# MK12_RelayShield.net
KiCad netlist of a schematic drawn in EAGLE
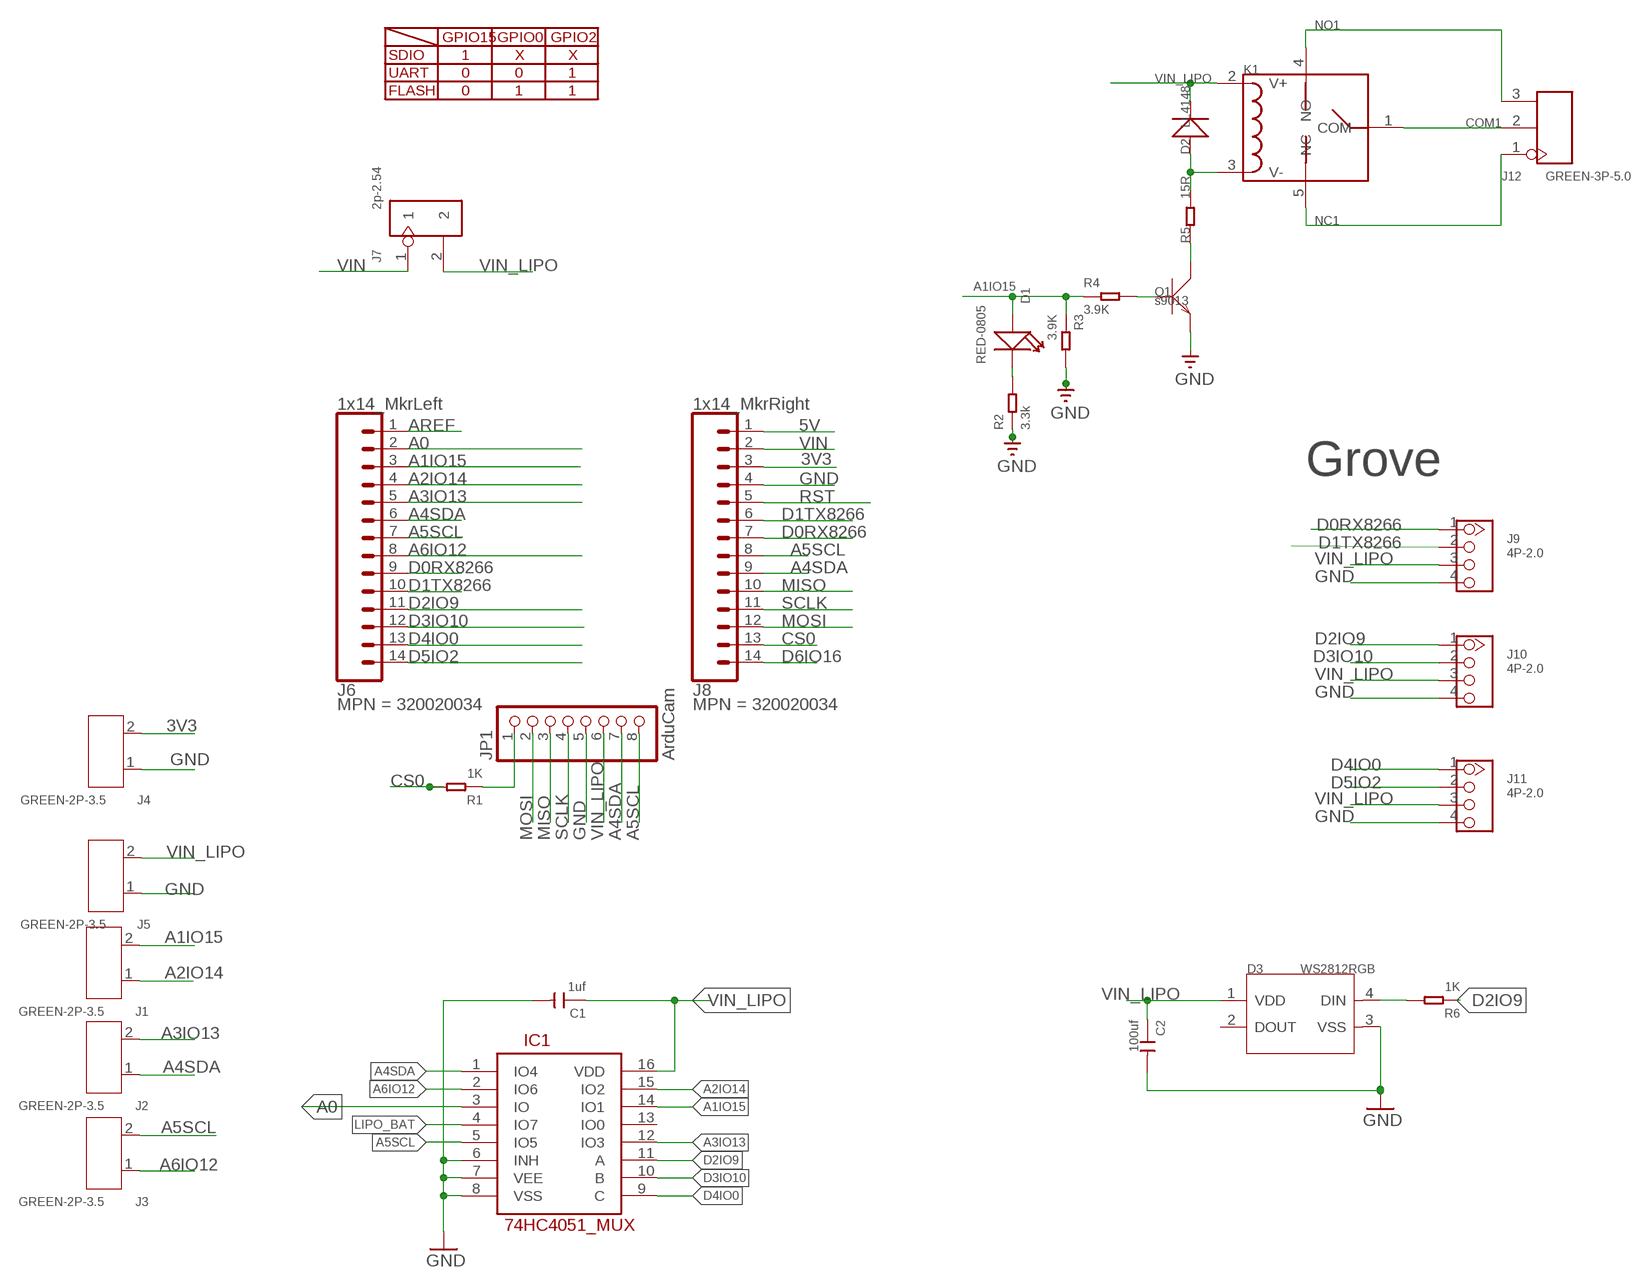
[diagram p0: schematic, sheet 1]

(export (version "E")
  (design (tool "Eeschema 10.0.6"))
  (components
    (comp (ref "C1")
      (value "1uf")
      (footprint "eagle-import:C0603")
      (fields (field (name "MPN") "CC0603KRX7R8BB105"))
      (libsource (lib "eagle-import") (part "CERAMIC-1UF-25V-10%-X7R(0603)"))
    )
    (comp (ref "C2")
      (value "100uf")
      (footprint "eagle-import:C1206")
      (fields (field (name "MPN") "GRM31CR60J107ME39L"))
      (libsource (lib "eagle-import") (part "CERAMIC-100UF-6.3V-20%-X5R(1206)"))
    )
    (comp (ref "D1")
      (value "RED-0805")
      (footprint "eagle-import:LED-0805")
      (fields (field (name "MPN") "17-215SURC/S530-A2/TR8"))
      (libsource (lib "eagle-import") (part "SMD-LED-CLEAR-RED(0805)"))
    )
    (comp (ref "D2")
      (value "LL4148")
      (footprint "eagle-import:LL-34")
      (libsource (lib "eagle-import") (part "D'1N4148-SMD'"))
    )
    (comp (ref "D3")
      (value "WS2812RGB")
      (footprint "eagle-import:LED4-SMD-5050")
      (libsource (lib "eagle-import") (part "SMD-RGB-LED-4P'WS2812B'"))
    )
    (comp (ref "IC1")
      (value "74HC4051_MUX")
      (footprint "eagle-import:SPARKFUN_SO16")
      (libsource (lib "eagle-import") (part "SPARKFUN_74HC4051_MUX"))
    )
    (comp (ref "J1")
      (value "GREEN-2P-3.5")
      (footprint "eagle-import:H2-3.5-7.0X7.0MM")
      (libsource (lib "eagle-import") (part "SCREW-TERMINAL-GREEN(2P-3.5)"))
    )
    (comp (ref "J2")
      (value "GREEN-2P-3.5")
      (footprint "eagle-import:H2-3.5-7.0X7.0MM")
      (libsource (lib "eagle-import") (part "SCREW-TERMINAL-GREEN(2P-3.5)"))
    )
    (comp (ref "J3")
      (value "GREEN-2P-3.5")
      (footprint "eagle-import:H2-3.5-7.0X7.0MM")
      (libsource (lib "eagle-import") (part "SCREW-TERMINAL-GREEN(2P-3.5)"))
    )
    (comp (ref "J4")
      (value "GREEN-2P-3.5")
      (footprint "eagle-import:H2-3.5-7.0X7.0MM")
      (libsource (lib "eagle-import") (part "SCREW-TERMINAL-GREEN(2P-3.5)"))
    )
    (comp (ref "J5")
      (value "GREEN-2P-3.5")
      (footprint "eagle-import:H2-3.5-7.0X7.0MM")
      (libsource (lib "eagle-import") (part "SCREW-TERMINAL-GREEN(2P-3.5)"))
    )
    (comp (ref "J6")
      (value "1x14_MkrLeft")
      (footprint "eagle-import:1X14_LOCK")
      (fields (field (name "MPN") "320020034"))
      (libsource (lib "eagle-import") (part "CONN_14LOCK"))
    )
    (comp (ref "J7")
      (value "2p-2.54")
      (footprint "eagle-import:H2-2.54")
      (fields (field (name "MPN") "P125-1102A0BS116A1"))
      (libsource (lib "eagle-import") (part "DIP-BLACK-MALE-HEADER-VERT(2P-2.54)"))
    )
    (comp (ref "J8")
      (value "1x14_MkrRight")
      (footprint "eagle-import:1X14_LOCK")
      (fields (field (name "MPN") "320020034"))
      (libsource (lib "eagle-import") (part "CONN_14LOCK"))
    )
    (comp (ref "J9")
      (value "4P-2.0")
      (footprint "eagle-import:HW4-2.0")
      (libsource (lib "eagle-import") (part "GROVE-CONNECTOR-DIP(4P-2.0)"))
    )
    (comp (ref "J10")
      (value "4P-2.0")
      (footprint "eagle-import:HW4-2.0")
      (libsource (lib "eagle-import") (part "GROVE-CONNECTOR-DIP(4P-2.0)"))
    )
    (comp (ref "J11")
      (value "4P-2.0")
      (footprint "eagle-import:HW4-2.0")
      (libsource (lib "eagle-import") (part "GROVE-CONNECTOR-DIP(4P-2.0)"))
    )
    (comp (ref "J12")
      (value "GREEN-3P-5.0")
      (footprint "eagle-import:H3-5.0-15.5X8.0MM")
      (libsource (lib "eagle-import") (part "SCREW-TERMINAL-GREEN(3P-5.0)"))
    )
    (comp (ref "JP1")
      (value "ArduCam")
      (footprint "eagle-import:MILLER_1X08-LOCK")
      (libsource (lib "eagle-import") (part "MILLER_PINHD-1X8LOCK"))
    )
    (comp (ref "K1")
      (value "RELAY-HLS8L-DC5V-S-CHLS8L-DC5V-S-C")
      (footprint "eagle-import:REY5-19.0X15.0X15.0MM")
      (libsource (lib "eagle-import") (part "RELAY-HLS8L-DC5V-S-CHLS8L-DC5V-S-C"))
    )
    (comp (ref "Q1")
      (value "s9013")
      (footprint "eagle-import:SOT23")
      (libsource (lib "eagle-import") (part "TRANSISTOR-NPN-SOT23"))
    )
    (comp (ref "R1")
      (value "1K")
      (footprint "eagle-import:R0805")
      (fields (field (name "MPN") "RC0805JR-071KL"))
      (libsource (lib "eagle-import") (part "SMD-RES-1K-5%-1/8W(0805)"))
    )
    (comp (ref "R2")
      (value "3.3k")
      (footprint "eagle-import:R0603")
      (libsource (lib "eagle-import") (part "SMD-RES-3.3K-5%-1/10W(0603)"))
    )
    (comp (ref "R3")
      (value "3.9K")
      (footprint "eagle-import:R0603")
      (fields (field (name "MPN") "RC0603JR-073K9L"))
      (libsource (lib "eagle-import") (part "SMD-RES-3.9K-5%-1/10W(0603)"))
    )
    (comp (ref "R4")
      (value "3.9K")
      (footprint "eagle-import:R0603")
      (fields (field (name "MPN") "RC0603JR-073K9L"))
      (libsource (lib "eagle-import") (part "SMD-RES-3.9K-5%-1/10W(0603)"))
    )
    (comp (ref "R5")
      (value "15R")
      (footprint "eagle-import:R0603")
      (libsource (lib "eagle-import") (part "R-0603"))
    )
    (comp (ref "R6")
      (value "1K")
      (footprint "eagle-import:R0805")
      (fields (field (name "MPN") "RC0805JR-071KL"))
      (libsource (lib "eagle-import") (part "SMD-RES-1K-5%-1/8W(0805)"))
    )
  )
  (nets
    (net (code "1") (name "/3V3") (class "Default")
      (node (ref "J4") (pin "2") (pinfunction "2_2") (pintype "bidirectional"))
      (node (ref "J8") (pin "3") (pinfunction "3_3") (pintype "passive"))
    )
    (net (code "2") (name "/5V") (class "Default")
      (node (ref "J8") (pin "1") (pinfunction "1_1") (pintype "passive"))
    )
    (net (code "3") (name "/AREF") (class "Default")
      (node (ref "J6") (pin "1") (pinfunction "1_1") (pintype "passive"))
    )
    (net (code "4") (name "/COM1") (class "Default")
      (node (ref "J12") (pin "2") (pinfunction "P$2_2") (pintype "bidirectional"))
      (node (ref "K1") (pin "1") (pinfunction "COM_1") (pintype "bidirectional"))
    )
    (net (code "5") (name "/CS0") (class "Default")
      (node (ref "J8") (pin "13") (pinfunction "13_13") (pintype "passive"))
      (node (ref "R1") (pin "2") (pinfunction "2_2") (pintype "passive"))
    )
    (net (code "6") (name "/D0RX8266") (class "Default")
      (node (ref "J6") (pin "9") (pinfunction "9_9") (pintype "passive"))
      (node (ref "J8") (pin "7") (pinfunction "7_7") (pintype "passive"))
      (node (ref "J9") (pin "1") (pinfunction "1_1") (pintype "bidirectional"))
    )
    (net (code "7") (name "/D1TX8266") (class "Default")
      (node (ref "J6") (pin "10") (pinfunction "10_10") (pintype "passive"))
      (node (ref "J8") (pin "6") (pinfunction "6_6") (pintype "passive"))
      (node (ref "J9") (pin "2") (pinfunction "2_2") (pintype "bidirectional"))
    )
    (net (code "8") (name "/D5IO2") (class "Default")
      (node (ref "J11") (pin "2") (pinfunction "2_2") (pintype "bidirectional"))
      (node (ref "J6") (pin "14") (pinfunction "14_14") (pintype "passive"))
    )
    (net (code "9") (name "/D6IO16") (class "Default")
      (node (ref "J8") (pin "14") (pinfunction "14_14") (pintype "passive"))
    )
    (net (code "10") (name "/MISO") (class "Default")
      (node (ref "J8") (pin "10") (pinfunction "10_10") (pintype "passive"))
      (node (ref "JP1") (pin "3") (pinfunction "3_3") (pintype "passive"))
    )
    (net (code "11") (name "/MOSI") (class "Default")
      (node (ref "J8") (pin "12") (pinfunction "12_12") (pintype "passive"))
      (node (ref "JP1") (pin "2") (pinfunction "2_2") (pintype "passive"))
    )
    (net (code "12") (name "/NC1") (class "Default")
      (node (ref "J12") (pin "1") (pinfunction "P$1_1") (pintype "bidirectional"))
      (node (ref "K1") (pin "5") (pinfunction "NC_5") (pintype "bidirectional"))
    )
    (net (code "13") (name "/NO1") (class "Default")
      (node (ref "J12") (pin "3") (pinfunction "P$3_3") (pintype "bidirectional"))
      (node (ref "K1") (pin "4") (pinfunction "NO_4") (pintype "bidirectional"))
    )
    (net (code "14") (name "/RST") (class "Default")
      (node (ref "J8") (pin "5") (pinfunction "5_5") (pintype "passive"))
    )
    (net (code "15") (name "/SCLK") (class "Default")
      (node (ref "J8") (pin "11") (pinfunction "11_11") (pintype "passive"))
      (node (ref "JP1") (pin "4") (pinfunction "4_4") (pintype "passive"))
    )
    (net (code "16") (name "/VIN") (class "Default")
      (node (ref "J7") (pin "1") (pinfunction "1_1") (pintype "bidirectional"))
      (node (ref "J8") (pin "2") (pinfunction "2_2") (pintype "passive"))
    )
    (net (code "17") (name "A0") (class "Default")
      (node (ref "IC1") (pin "3") (pinfunction "IO_3") (pintype "bidirectional"))
      (node (ref "J6") (pin "2") (pinfunction "2_2") (pintype "passive"))
    )
    (net (code "18") (name "A1IO15") (class "Default")
      (node (ref "D1") (pin "+") (pinfunction "+_+") (pintype "passive"))
      (node (ref "IC1") (pin "14") (pinfunction "IO1_14") (pintype "bidirectional"))
      (node (ref "J1") (pin "2") (pinfunction "2_2") (pintype "bidirectional"))
      (node (ref "J6") (pin "3") (pinfunction "3_3") (pintype "passive"))
      (node (ref "R3") (pin "1") (pinfunction "1_1") (pintype "passive"))
      (node (ref "R4") (pin "1") (pinfunction "1_1") (pintype "passive"))
    )
    (net (code "19") (name "A2IO14") (class "Default")
      (node (ref "IC1") (pin "15") (pinfunction "IO2_15") (pintype "bidirectional"))
      (node (ref "J1") (pin "1") (pinfunction "1_1") (pintype "bidirectional"))
      (node (ref "J6") (pin "4") (pinfunction "4_4") (pintype "passive"))
    )
    (net (code "20") (name "A3IO13") (class "Default")
      (node (ref "IC1") (pin "12") (pinfunction "IO3_12") (pintype "bidirectional"))
      (node (ref "J2") (pin "2") (pinfunction "2_2") (pintype "bidirectional"))
      (node (ref "J6") (pin "5") (pinfunction "5_5") (pintype "passive"))
    )
    (net (code "21") (name "A4SDA") (class "Default")
      (node (ref "IC1") (pin "1") (pinfunction "IO4_1") (pintype "bidirectional"))
      (node (ref "J2") (pin "1") (pinfunction "1_1") (pintype "bidirectional"))
      (node (ref "J6") (pin "6") (pinfunction "6_6") (pintype "passive"))
      (node (ref "J8") (pin "9") (pinfunction "9_9") (pintype "passive"))
      (node (ref "JP1") (pin "7") (pinfunction "7_7") (pintype "passive"))
    )
    (net (code "22") (name "A5SCL") (class "Default")
      (node (ref "IC1") (pin "5") (pinfunction "IO5_5") (pintype "bidirectional"))
      (node (ref "J3") (pin "2") (pinfunction "2_2") (pintype "bidirectional"))
      (node (ref "J6") (pin "7") (pinfunction "7_7") (pintype "passive"))
      (node (ref "J8") (pin "8") (pinfunction "8_8") (pintype "passive"))
      (node (ref "JP1") (pin "8") (pinfunction "8_8") (pintype "passive"))
    )
    (net (code "23") (name "A6IO12") (class "Default")
      (node (ref "IC1") (pin "2") (pinfunction "IO6_2") (pintype "bidirectional"))
      (node (ref "J3") (pin "1") (pinfunction "1_1") (pintype "bidirectional"))
      (node (ref "J6") (pin "8") (pinfunction "8_8") (pintype "passive"))
    )
    (net (code "24") (name "D2IO9") (class "Default")
      (node (ref "IC1") (pin "11") (pinfunction "A_11") (pintype "bidirectional"))
      (node (ref "J10") (pin "1") (pinfunction "1_1") (pintype "bidirectional"))
      (node (ref "J6") (pin "11") (pinfunction "11_11") (pintype "passive"))
      (node (ref "R6") (pin "1") (pinfunction "1_1") (pintype "passive"))
    )
    (net (code "25") (name "D3IO10") (class "Default")
      (node (ref "IC1") (pin "10") (pinfunction "B_10") (pintype "bidirectional"))
      (node (ref "J10") (pin "2") (pinfunction "2_2") (pintype "bidirectional"))
      (node (ref "J6") (pin "12") (pinfunction "12_12") (pintype "passive"))
    )
    (net (code "26") (name "D4IO0") (class "Default")
      (node (ref "IC1") (pin "9") (pinfunction "C_9") (pintype "bidirectional"))
      (node (ref "J11") (pin "1") (pinfunction "1_1") (pintype "bidirectional"))
      (node (ref "J6") (pin "13") (pinfunction "13_13") (pintype "passive"))
    )
    (net (code "27") (name "GND") (class "Default")
      (node (ref "C1") (pin "2") (pinfunction "2_2") (pintype "passive"))
      (node (ref "C2") (pin "2") (pinfunction "2_2") (pintype "passive"))
      (node (ref "D3") (pin "3") (pinfunction "VSS_3") (pintype "bidirectional"))
      (node (ref "IC1") (pin "6") (pinfunction "INH_6") (pintype "bidirectional"))
      (node (ref "IC1") (pin "7") (pinfunction "VEE_7") (pintype "bidirectional"))
      (node (ref "IC1") (pin "8") (pinfunction "VSS_8") (pintype "bidirectional"))
      (node (ref "J10") (pin "4") (pinfunction "4_4") (pintype "bidirectional"))
      (node (ref "J11") (pin "4") (pinfunction "4_4") (pintype "bidirectional"))
      (node (ref "J4") (pin "1") (pinfunction "1_1") (pintype "bidirectional"))
      (node (ref "J5") (pin "1") (pinfunction "1_1") (pintype "bidirectional"))
      (node (ref "J8") (pin "4") (pinfunction "4_4") (pintype "passive"))
      (node (ref "J9") (pin "4") (pinfunction "4_4") (pintype "bidirectional"))
      (node (ref "JP1") (pin "5") (pinfunction "5_5") (pintype "passive"))
      (node (ref "Q1") (pin "2") (pinfunction "E_2") (pintype "passive"))
      (node (ref "R2") (pin "1") (pinfunction "1_1") (pintype "passive"))
      (node (ref "R3") (pin "2") (pinfunction "2_2") (pintype "passive"))
    )
    (net (code "28") (name "LIPO_BAT") (class "Default")
      (node (ref "IC1") (pin "4") (pinfunction "IO7_4") (pintype "bidirectional"))
    )
    (net (code "29") (name "Net-(D1-Pad-)") (class "Default")
      (node (ref "D1") (pin "-") (pinfunction "-_-") (pintype "passive"))
      (node (ref "R2") (pin "2") (pinfunction "2_2") (pintype "passive"))
    )
    (net (code "30") (name "Net-(D2-+)") (class "Default")
      (node (ref "D2") (pin "A") (pinfunction "+_A") (pintype "passive"))
      (node (ref "K1") (pin "3") (pinfunction "V-_3") (pintype "bidirectional"))
      (node (ref "R5") (pin "2") (pinfunction "2_2") (pintype "passive"))
    )
    (net (code "31") (name "Net-(D3-DIN)") (class "Default")
      (node (ref "D3") (pin "4") (pinfunction "DIN_4") (pintype "bidirectional"))
      (node (ref "R6") (pin "2") (pinfunction "2_2") (pintype "passive"))
    )
    (net (code "32") (name "Net-(JP1-Pad1)") (class "Default")
      (node (ref "JP1") (pin "1") (pinfunction "1_1") (pintype "passive"))
      (node (ref "R1") (pin "1") (pinfunction "1_1") (pintype "passive"))
    )
    (net (code "33") (name "Net-(Q1-B)") (class "Default")
      (node (ref "Q1") (pin "1") (pinfunction "B_1") (pintype "passive"))
      (node (ref "R4") (pin "2") (pinfunction "2_2") (pintype "passive"))
    )
    (net (code "34") (name "Net-(Q1-C)") (class "Default")
      (node (ref "Q1") (pin "3") (pinfunction "C_3") (pintype "passive"))
      (node (ref "R5") (pin "1") (pinfunction "1_1") (pintype "passive"))
    )
    (net (code "35") (name "VIN_LIPO") (class "Default")
      (node (ref "C1") (pin "1") (pinfunction "1_1") (pintype "passive"))
      (node (ref "C2") (pin "1") (pinfunction "1_1") (pintype "passive"))
      (node (ref "D2") (pin "C") (pinfunction "-_C") (pintype "passive"))
      (node (ref "D3") (pin "1") (pinfunction "VDD_1") (pintype "bidirectional"))
      (node (ref "IC1") (pin "16") (pinfunction "VDD_16") (pintype "bidirectional"))
      (node (ref "J10") (pin "3") (pinfunction "3_3") (pintype "bidirectional"))
      (node (ref "J11") (pin "3") (pinfunction "3_3") (pintype "bidirectional"))
      (node (ref "J5") (pin "2") (pinfunction "2_2") (pintype "bidirectional"))
      (node (ref "J7") (pin "2") (pinfunction "2_2") (pintype "bidirectional"))
      (node (ref "J9") (pin "3") (pinfunction "3_3") (pintype "bidirectional"))
      (node (ref "JP1") (pin "6") (pinfunction "6_6") (pintype "passive"))
      (node (ref "K1") (pin "2") (pinfunction "V+_2") (pintype "bidirectional"))
    )
    (net (code "36") (name "unconnected-(D3-DOUT-Pad2)") (class "Default")
      (node (ref "D3") (pin "2") (pinfunction "DOUT_2") (pintype "bidirectional"))
    )
    (net (code "37") (name "unconnected-(IC1-IO0-Pad13)") (class "Default")
      (node (ref "IC1") (pin "13") (pinfunction "IO0_13") (pintype "bidirectional"))
    )
  )
)
